# retros.net
KiCad netlist of a schematic drawn in Altium Designer
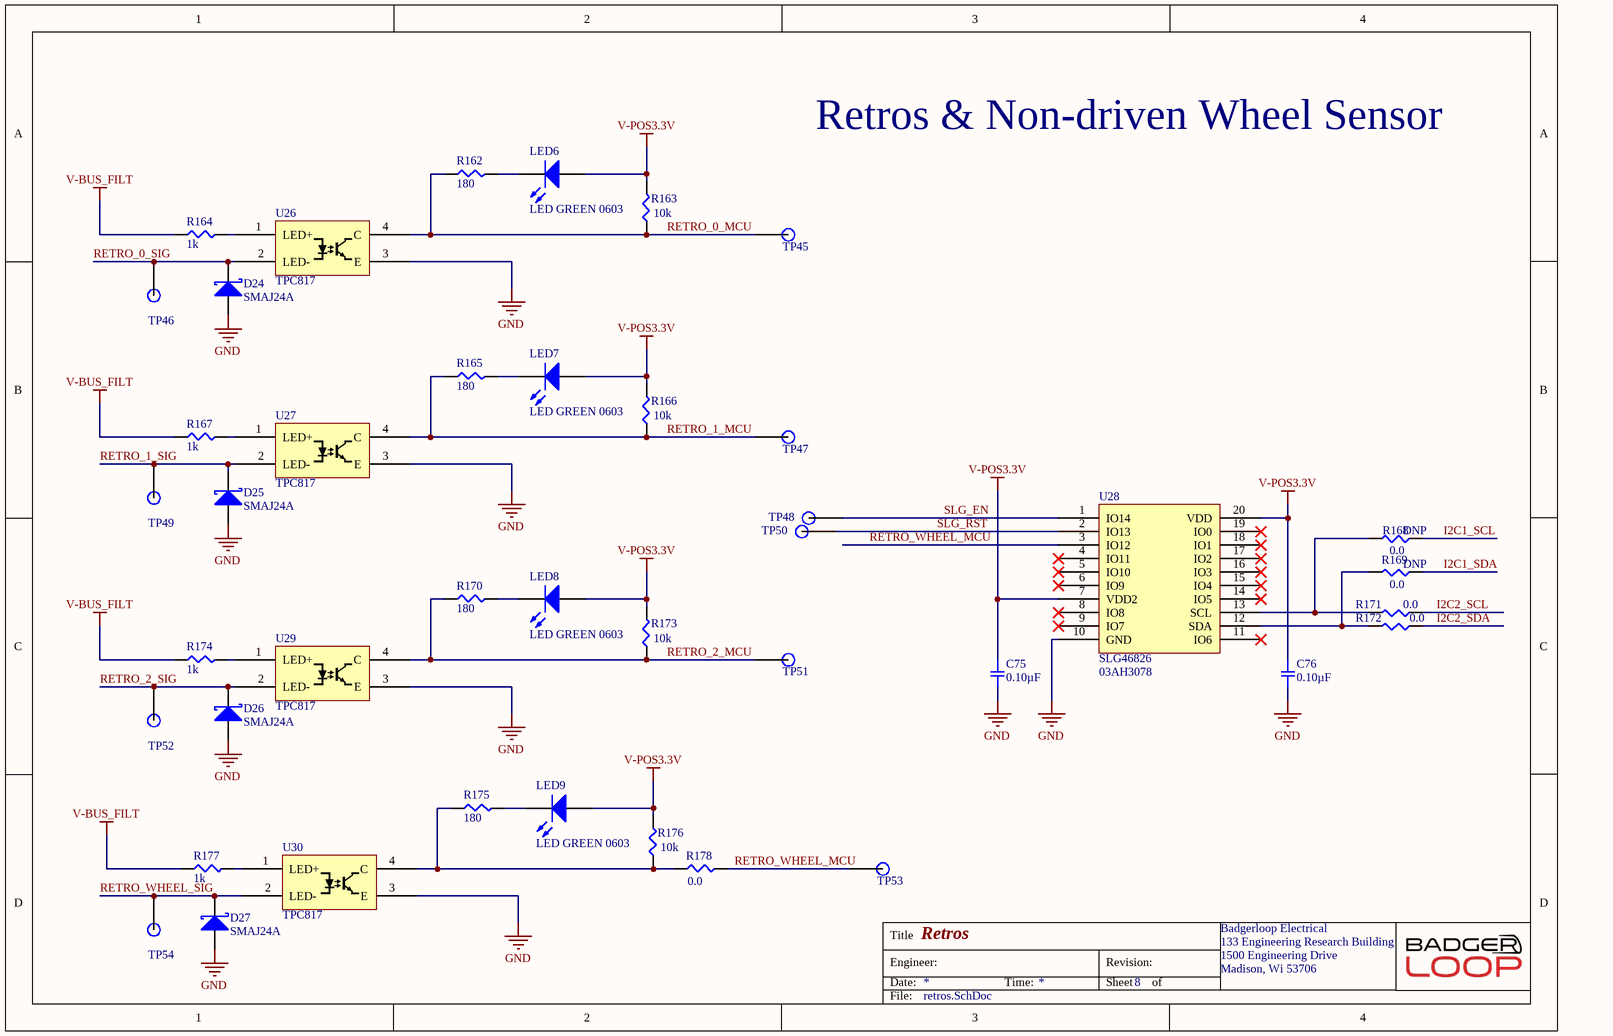
[diagram p0: retros.SchDoc]

(export (version "E")
  (design (tool "Eeschema 10.0.6"))
  (components
    (comp (ref "C75")
      (value "0.10µF")
      (footprint "SMD-0805C")
      (description "CAP CER 0.1UF 25V X7R 0805")
      (fields
        (field (name "DIGI-KEY PART NUMBER") "490-12754-1-ND")
        (field (name "PART NUMBER") "GRM219R71E104KA01D")
      )
      (libsource (lib "capacitors") (part "GRM219R71E104KA01D"))
    )
    (comp (ref "C76")
      (value "0.10µF")
      (footprint "SMD-0805C")
      (description "CAP CER 0.1UF 25V X7R 0805")
      (fields
        (field (name "DIGI-KEY PART NUMBER") "490-12754-1-ND")
        (field (name "PART NUMBER") "GRM219R71E104KA01D")
      )
      (libsource (lib "capacitors") (part "GRM219R71E104KA01D"))
    )
    (comp (ref "D24")
      (value "SMAJ24A")
      (footprint "INDM5026X18N")
      (description "TVS DIODE 24V 38.9V DO214AC")
      (fields (field (name "MANUFACTURER") "LittelFuse Inc"))
      (libsource (lib "misc") (part "SMAJ24A"))
    )
    (comp (ref "D25")
      (value "SMAJ24A")
      (footprint "INDM5026X18N")
      (description "TVS DIODE 24V 38.9V DO214AC")
      (fields (field (name "MANUFACTURER") "LittelFuse Inc"))
      (libsource (lib "misc") (part "SMAJ24A"))
    )
    (comp (ref "D26")
      (value "SMAJ24A")
      (footprint "INDM5026X18N")
      (description "TVS DIODE 24V 38.9V DO214AC")
      (fields (field (name "MANUFACTURER") "LittelFuse Inc"))
      (libsource (lib "misc") (part "SMAJ24A"))
    )
    (comp (ref "D27")
      (value "SMAJ24A")
      (footprint "INDM5026X18N")
      (description "TVS DIODE 24V 38.9V DO214AC")
      (fields (field (name "MANUFACTURER") "LittelFuse Inc"))
      (libsource (lib "misc") (part "SMAJ24A"))
    )
    (comp (ref "LED6")
      (value "LED GREEN 0603")
      (footprint "LED 0603 GREEN")
      (fields (field (name "MANUFACTURER") "Lite-On Inc."))
      (libsource (lib "misc") (part "LED GREEN 0603"))
    )
    (comp (ref "LED7")
      (value "LED GREEN 0603")
      (footprint "LED 0603 GREEN")
      (fields (field (name "MANUFACTURER") "Lite-On Inc."))
      (libsource (lib "misc") (part "LED GREEN 0603"))
    )
    (comp (ref "LED8")
      (value "LED GREEN 0603")
      (footprint "LED 0603 GREEN")
      (fields (field (name "MANUFACTURER") "Lite-On Inc."))
      (libsource (lib "misc") (part "LED GREEN 0603"))
    )
    (comp (ref "LED9")
      (value "LED GREEN 0603")
      (footprint "LED 0603 GREEN")
      (fields (field (name "MANUFACTURER") "Lite-On Inc."))
      (libsource (lib "misc") (part "LED GREEN 0603"))
    )
    (comp (ref "R162")
      (value "180")
      (footprint "SMD-0805-RES")
      (description "RES SMD 180 OHM 1% 1/8W 0805")
      (fields (field (name "PART NUMBER") "ERJ-6ENF1800V") (field (name "DIGI-KEY PART NUMBER") "P180CCT-ND"))
      (libsource (lib "resistors") (part "ERJ-6ENF1800V"))
    )
    (comp (ref "R163")
      (value "10k")
      (footprint "SMD-0805-RES")
      (description "RES SMD 10K OHM 5% 1/8W 0805")
      (fields (field (name "PART NUMBER") "ERJ-6GEYJ103V") (field (name "DIGI-KEY PART NUMBER") "P10KACT-ND"))
      (libsource (lib "resistors") (part "ERJ-6GEYJ103V"))
    )
    (comp (ref "R164")
      (value "1k")
      (footprint "SMD-0805-RES")
      (description "RES SMD 1K OHM 1% 1/8W 0805")
      (fields
        (field (name "PART NUMBER") "ERJ-6ENF1001V")
        (field (name "DIGI-KEY PART NUMBER") "P1.00KCCT-ND")
      )
      (libsource (lib "resistors") (part "ERJ-6ENF1001V"))
    )
    (comp (ref "R165")
      (value "180")
      (footprint "SMD-0805-RES")
      (description "RES SMD 180 OHM 1% 1/8W 0805")
      (fields (field (name "PART NUMBER") "ERJ-6ENF1800V") (field (name "DIGI-KEY PART NUMBER") "P180CCT-ND"))
      (libsource (lib "resistors") (part "ERJ-6ENF1800V"))
    )
    (comp (ref "R166")
      (value "10k")
      (footprint "SMD-0805-RES")
      (description "RES SMD 10K OHM 5% 1/8W 0805")
      (fields (field (name "PART NUMBER") "ERJ-6GEYJ103V") (field (name "DIGI-KEY PART NUMBER") "P10KACT-ND"))
      (libsource (lib "resistors") (part "ERJ-6GEYJ103V"))
    )
    (comp (ref "R167")
      (value "1k")
      (footprint "SMD-0805-RES")
      (description "RES SMD 1K OHM 1% 1/8W 0805")
      (fields
        (field (name "PART NUMBER") "ERJ-6ENF1001V")
        (field (name "DIGI-KEY PART NUMBER") "P1.00KCCT-ND")
      )
      (libsource (lib "resistors") (part "ERJ-6ENF1001V"))
    )
    (comp (ref "R168")
      (value "0.0")
      (footprint "SMD-0805-RES")
      (description "RES SMD 0.0 OHM JUMPER 1/8W 0805")
      (fields
        (field (name "PART NUMBER") "ERJ-6GEY0R00V")
        (field (name "DIGI-KEY PART NUMBER") "P0.0ACT-ND")
        (field (name "DNP") "DNP")
      )
      (libsource (lib "resistors") (part "ERJ-6GEY0R00V"))
    )
    (comp (ref "R169")
      (value "0.0")
      (footprint "SMD-0805-RES")
      (description "RES SMD 0.0 OHM JUMPER 1/8W 0805")
      (fields
        (field (name "PART NUMBER") "ERJ-6GEY0R00V")
        (field (name "DIGI-KEY PART NUMBER") "P0.0ACT-ND")
        (field (name "DNP") "DNP")
      )
      (libsource (lib "resistors") (part "ERJ-6GEY0R00V"))
    )
    (comp (ref "R170")
      (value "180")
      (footprint "SMD-0805-RES")
      (description "RES SMD 180 OHM 1% 1/8W 0805")
      (fields (field (name "PART NUMBER") "ERJ-6ENF1800V") (field (name "DIGI-KEY PART NUMBER") "P180CCT-ND"))
      (libsource (lib "resistors") (part "ERJ-6ENF1800V"))
    )
    (comp (ref "R171")
      (value "0.0")
      (footprint "SMD-0805-RES")
      (description "RES SMD 0.0 OHM JUMPER 1/8W 0805")
      (fields (field (name "PART NUMBER") "ERJ-6GEY0R00V") (field (name "DIGI-KEY PART NUMBER") "P0.0ACT-ND"))
      (libsource (lib "resistors") (part "ERJ-6GEY0R00V"))
    )
    (comp (ref "R172")
      (value "0.0")
      (footprint "SMD-0805-RES")
      (description "RES SMD 0.0 OHM JUMPER 1/8W 0805")
      (fields (field (name "PART NUMBER") "ERJ-6GEY0R00V") (field (name "DIGI-KEY PART NUMBER") "P0.0ACT-ND"))
      (libsource (lib "resistors") (part "ERJ-6GEY0R00V"))
    )
    (comp (ref "R173")
      (value "10k")
      (footprint "SMD-0805-RES")
      (description "RES SMD 10K OHM 5% 1/8W 0805")
      (fields (field (name "PART NUMBER") "ERJ-6GEYJ103V") (field (name "DIGI-KEY PART NUMBER") "P10KACT-ND"))
      (libsource (lib "resistors") (part "ERJ-6GEYJ103V"))
    )
    (comp (ref "R174")
      (value "1k")
      (footprint "SMD-0805-RES")
      (description "RES SMD 1K OHM 1% 1/8W 0805")
      (fields
        (field (name "PART NUMBER") "ERJ-6ENF1001V")
        (field (name "DIGI-KEY PART NUMBER") "P1.00KCCT-ND")
      )
      (libsource (lib "resistors") (part "ERJ-6ENF1001V"))
    )
    (comp (ref "R175")
      (value "180")
      (footprint "SMD-0805-RES")
      (description "RES SMD 180 OHM 1% 1/8W 0805")
      (fields (field (name "PART NUMBER") "ERJ-6ENF1800V") (field (name "DIGI-KEY PART NUMBER") "P180CCT-ND"))
      (libsource (lib "resistors") (part "ERJ-6ENF1800V"))
    )
    (comp (ref "R176")
      (value "10k")
      (footprint "SMD-0805-RES")
      (description "RES SMD 10K OHM 5% 1/8W 0805")
      (fields (field (name "PART NUMBER") "ERJ-6GEYJ103V") (field (name "DIGI-KEY PART NUMBER") "P10KACT-ND"))
      (libsource (lib "resistors") (part "ERJ-6GEYJ103V"))
    )
    (comp (ref "R177")
      (value "1k")
      (footprint "SMD-0805-RES")
      (description "RES SMD 1K OHM 1% 1/8W 0805")
      (fields
        (field (name "PART NUMBER") "ERJ-6ENF1001V")
        (field (name "DIGI-KEY PART NUMBER") "P1.00KCCT-ND")
      )
      (libsource (lib "resistors") (part "ERJ-6ENF1001V"))
    )
    (comp (ref "R178")
      (value "0.0")
      (footprint "SMD-0805-RES")
      (description "RES SMD 0.0 OHM JUMPER 1/8W 0805")
      (fields (field (name "PART NUMBER") "ERJ-6GEY0R00V") (field (name "DIGI-KEY PART NUMBER") "P0.0ACT-ND"))
      (libsource (lib "resistors") (part "ERJ-6GEY0R00V"))
    )
    (comp (ref "TP45")
      (value "TP")
      (footprint "Test Point")
      (description "SMD TEST POINT")
      (libsource (lib "misc") (part "TP"))
    )
    (comp (ref "TP46")
      (value "TP")
      (footprint "Test Point")
      (description "SMD TEST POINT")
      (libsource (lib "misc") (part "TP"))
    )
    (comp (ref "TP47")
      (value "TP")
      (footprint "Test Point")
      (description "SMD TEST POINT")
      (libsource (lib "misc") (part "TP"))
    )
    (comp (ref "TP48")
      (value "TP")
      (footprint "Test Point")
      (description "SMD TEST POINT")
      (libsource (lib "misc") (part "TP"))
    )
    (comp (ref "TP49")
      (value "TP")
      (footprint "Test Point")
      (description "SMD TEST POINT")
      (libsource (lib "misc") (part "TP"))
    )
    (comp (ref "TP50")
      (value "TP")
      (footprint "Test Point")
      (description "SMD TEST POINT")
      (libsource (lib "misc") (part "TP"))
    )
    (comp (ref "TP51")
      (value "TP")
      (footprint "Test Point")
      (description "SMD TEST POINT")
      (libsource (lib "misc") (part "TP"))
    )
    (comp (ref "TP52")
      (value "TP")
      (footprint "Test Point")
      (description "SMD TEST POINT")
      (libsource (lib "misc") (part "TP"))
    )
    (comp (ref "TP53")
      (value "TP")
      (footprint "Test Point")
      (description "SMD TEST POINT")
      (libsource (lib "misc") (part "TP"))
    )
    (comp (ref "TP54")
      (value "TP")
      (footprint "Test Point")
      (description "SMD TEST POINT")
      (libsource (lib "misc") (part "TP"))
    )
    (comp (ref "U26")
      (value "TPC817")
      (footprint "SOT200P1005X328-5N")
      (description "OPTOISO 5KV TRANS 4SOP")
      (fields (field (name "MANUFACTURER") "Taiwan Semi"))
      (libsource (lib "ic") (part "TPC817"))
    )
    (comp (ref "U27")
      (value "TPC817")
      (footprint "SOT200P1005X328-5N")
      (description "OPTOISO 5KV TRANS 4SOP")
      (fields (field (name "MANUFACTURER") "Taiwan Semi"))
      (libsource (lib "ic") (part "TPC817"))
    )
    (comp (ref "U28")
      (value "SLG46826")
      (footprint "SOP65P640X175-20N")
      (description "GreenPAK Programmable Mixed Signal Matrix with In-System Programmability")
      (fields
        (field (name "MANUFACTURER") "Dialog Semiconductor")
        (field (name "MANUFACTURER PART NUMBER") "SLG46826V-SKT")
        (field (name "SUPPLIER PART NUMBER 1") "03AH3078")
      )
      (libsource (lib "ic") (part "SLG46826"))
    )
    (comp (ref "U29")
      (value "TPC817")
      (footprint "SOT200P1005X328-5N")
      (description "OPTOISO 5KV TRANS 4SOP")
      (fields (field (name "MANUFACTURER") "Taiwan Semi"))
      (libsource (lib "ic") (part "TPC817"))
    )
    (comp (ref "U30")
      (value "TPC817")
      (footprint "SOT200P1005X328-5N")
      (description "OPTOISO 5KV TRANS 4SOP")
      (fields (field (name "MANUFACTURER") "Taiwan Semi"))
      (libsource (lib "ic") (part "TPC817"))
    )
  )
  (nets
    (net (code "1") (name "/I2C1_SCL") (class "Default")
      (node (ref "R168") (pin "1") (pinfunction "1_1") (pintype "passive"))
    )
    (net (code "2") (name "/I2C1_SDA") (class "Default")
      (node (ref "R169") (pin "1") (pinfunction "1_1") (pintype "passive"))
    )
    (net (code "3") (name "/I2C2_SCL") (class "Default")
      (node (ref "R171") (pin "1") (pinfunction "1_1") (pintype "passive"))
    )
    (net (code "4") (name "/I2C2_SDA") (class "Default")
      (node (ref "R172") (pin "1") (pinfunction "1_1") (pintype "passive"))
    )
    (net (code "5") (name "/RETRO_0_MCU") (class "Default")
      (node (ref "R162") (pin "1") (pinfunction "1_1") (pintype "passive"))
      (node (ref "R163") (pin "1") (pinfunction "1_1") (pintype "passive"))
      (node (ref "TP45") (pin "1") (pinfunction "1_1") (pintype "passive"))
      (node (ref "U26") (pin "4") (pinfunction "C_4") (pintype "passive"))
    )
    (net (code "6") (name "/RETRO_0_SIG") (class "Default")
      (node (ref "D24") (pin "1") (pinfunction "A_1") (pintype "passive"))
      (node (ref "TP46") (pin "1") (pinfunction "1_1") (pintype "passive"))
      (node (ref "U26") (pin "2") (pinfunction "LED-_2") (pintype "passive"))
    )
    (net (code "7") (name "/RETRO_1_MCU") (class "Default")
      (node (ref "R165") (pin "1") (pinfunction "1_1") (pintype "passive"))
      (node (ref "R166") (pin "1") (pinfunction "1_1") (pintype "passive"))
      (node (ref "TP47") (pin "1") (pinfunction "1_1") (pintype "passive"))
      (node (ref "U27") (pin "4") (pinfunction "C_4") (pintype "passive"))
    )
    (net (code "8") (name "/RETRO_1_SIG") (class "Default")
      (node (ref "D25") (pin "1") (pinfunction "A_1") (pintype "passive"))
      (node (ref "TP49") (pin "1") (pinfunction "1_1") (pintype "passive"))
      (node (ref "U27") (pin "2") (pinfunction "LED-_2") (pintype "passive"))
    )
    (net (code "9") (name "/RETRO_2_MCU") (class "Default")
      (node (ref "R170") (pin "1") (pinfunction "1_1") (pintype "passive"))
      (node (ref "R173") (pin "1") (pinfunction "1_1") (pintype "passive"))
      (node (ref "TP51") (pin "1") (pinfunction "1_1") (pintype "passive"))
      (node (ref "U29") (pin "4") (pinfunction "C_4") (pintype "passive"))
    )
    (net (code "10") (name "/RETRO_2_SIG") (class "Default")
      (node (ref "D26") (pin "1") (pinfunction "A_1") (pintype "passive"))
      (node (ref "TP52") (pin "1") (pinfunction "1_1") (pintype "passive"))
      (node (ref "U29") (pin "2") (pinfunction "LED-_2") (pintype "passive"))
    )
    (net (code "11") (name "/RETRO_WHEEL_MCU") (class "Default")
      (node (ref "R178") (pin "2") (pinfunction "2_2") (pintype "passive"))
      (node (ref "TP53") (pin "1") (pinfunction "1_1") (pintype "passive"))
      (node (ref "U28") (pin "3") (pinfunction "IO12_3") (pintype "passive"))
    )
    (net (code "12") (name "/RETRO_WHEEL_SIG") (class "Default")
      (node (ref "D27") (pin "1") (pinfunction "A_1") (pintype "passive"))
      (node (ref "TP54") (pin "1") (pinfunction "1_1") (pintype "passive"))
      (node (ref "U30") (pin "2") (pinfunction "LED-_2") (pintype "passive"))
    )
    (net (code "13") (name "/SLG_EN") (class "Default")
      (node (ref "TP48") (pin "1") (pinfunction "1_1") (pintype "passive"))
      (node (ref "U28") (pin "1") (pinfunction "IO14_1") (pintype "passive"))
    )
    (net (code "14") (name "/SLG_RST") (class "Default")
      (node (ref "TP50") (pin "1") (pinfunction "1_1") (pintype "passive"))
      (node (ref "U28") (pin "2") (pinfunction "IO13_2") (pintype "passive"))
    )
    (net (code "15") (name "GND") (class "Default")
      (node (ref "C75") (pin "2") (pinfunction "2_2") (pintype "passive"))
      (node (ref "C76") (pin "2") (pinfunction "2_2") (pintype "passive"))
      (node (ref "D24") (pin "2") (pinfunction "K_2") (pintype "passive"))
      (node (ref "D25") (pin "2") (pinfunction "K_2") (pintype "passive"))
      (node (ref "D26") (pin "2") (pinfunction "K_2") (pintype "passive"))
      (node (ref "D27") (pin "2") (pinfunction "K_2") (pintype "passive"))
      (node (ref "U26") (pin "3") (pinfunction "E_3") (pintype "passive"))
      (node (ref "U27") (pin "3") (pinfunction "E_3") (pintype "passive"))
      (node (ref "U28") (pin "10") (pinfunction "GND_10") (pintype "passive"))
      (node (ref "U29") (pin "3") (pinfunction "E_3") (pintype "passive"))
      (node (ref "U30") (pin "3") (pinfunction "E_3") (pintype "passive"))
    )
    (net (code "16") (name "Net-(LED6-K)") (class "Default")
      (node (ref "LED6") (pin "2") (pinfunction "K_2") (pintype "passive"))
      (node (ref "R162") (pin "2") (pinfunction "2_2") (pintype "passive"))
    )
    (net (code "17") (name "Net-(LED7-K)") (class "Default")
      (node (ref "LED7") (pin "2") (pinfunction "K_2") (pintype "passive"))
      (node (ref "R165") (pin "2") (pinfunction "2_2") (pintype "passive"))
    )
    (net (code "18") (name "Net-(LED8-K)") (class "Default")
      (node (ref "LED8") (pin "2") (pinfunction "K_2") (pintype "passive"))
      (node (ref "R170") (pin "2") (pinfunction "2_2") (pintype "passive"))
    )
    (net (code "19") (name "Net-(LED9-K)") (class "Default")
      (node (ref "LED9") (pin "2") (pinfunction "K_2") (pintype "passive"))
      (node (ref "R175") (pin "2") (pinfunction "2_2") (pintype "passive"))
    )
    (net (code "20") (name "Net-(U26-LED+)") (class "Default")
      (node (ref "R164") (pin "2") (pinfunction "2_2") (pintype "passive"))
      (node (ref "U26") (pin "1") (pinfunction "LED+_1") (pintype "passive"))
    )
    (net (code "21") (name "Net-(U27-LED+)") (class "Default")
      (node (ref "R167") (pin "2") (pinfunction "2_2") (pintype "passive"))
      (node (ref "U27") (pin "1") (pinfunction "LED+_1") (pintype "passive"))
    )
    (net (code "22") (name "Net-(U28-SCL)") (class "Default")
      (node (ref "R168") (pin "2") (pinfunction "2_2") (pintype "passive"))
      (node (ref "R171") (pin "2") (pinfunction "2_2") (pintype "passive"))
      (node (ref "U28") (pin "13") (pinfunction "SCL_13") (pintype "passive"))
    )
    (net (code "23") (name "Net-(U28-SDA)") (class "Default")
      (node (ref "R169") (pin "2") (pinfunction "2_2") (pintype "passive"))
      (node (ref "R172") (pin "2") (pinfunction "2_2") (pintype "passive"))
      (node (ref "U28") (pin "12") (pinfunction "SDA_12") (pintype "passive"))
    )
    (net (code "24") (name "Net-(U29-LED+)") (class "Default")
      (node (ref "R174") (pin "2") (pinfunction "2_2") (pintype "passive"))
      (node (ref "U29") (pin "1") (pinfunction "LED+_1") (pintype "passive"))
    )
    (net (code "25") (name "Net-(U30-C)") (class "Default")
      (node (ref "R175") (pin "1") (pinfunction "1_1") (pintype "passive"))
      (node (ref "R176") (pin "1") (pinfunction "1_1") (pintype "passive"))
      (node (ref "R178") (pin "1") (pinfunction "1_1") (pintype "passive"))
      (node (ref "U30") (pin "4") (pinfunction "C_4") (pintype "passive"))
    )
    (net (code "26") (name "Net-(U30-LED+)") (class "Default")
      (node (ref "R177") (pin "2") (pinfunction "2_2") (pintype "passive"))
      (node (ref "U30") (pin "1") (pinfunction "LED+_1") (pintype "passive"))
    )
    (net (code "27") (name "V-BUS_FILT") (class "Default")
      (node (ref "R164") (pin "1") (pinfunction "1_1") (pintype "passive"))
      (node (ref "R167") (pin "1") (pinfunction "1_1") (pintype "passive"))
      (node (ref "R174") (pin "1") (pinfunction "1_1") (pintype "passive"))
      (node (ref "R177") (pin "1") (pinfunction "1_1") (pintype "passive"))
    )
    (net (code "28") (name "V-POS3.3V") (class "Default")
      (node (ref "C75") (pin "1") (pinfunction "1_1") (pintype "passive"))
      (node (ref "C76") (pin "1") (pinfunction "1_1") (pintype "passive"))
      (node (ref "LED6") (pin "1") (pinfunction "A_1") (pintype "passive"))
      (node (ref "LED7") (pin "1") (pinfunction "A_1") (pintype "passive"))
      (node (ref "LED8") (pin "1") (pinfunction "A_1") (pintype "passive"))
      (node (ref "LED9") (pin "1") (pinfunction "A_1") (pintype "passive"))
      (node (ref "R163") (pin "2") (pinfunction "2_2") (pintype "passive"))
      (node (ref "R166") (pin "2") (pinfunction "2_2") (pintype "passive"))
      (node (ref "R173") (pin "2") (pinfunction "2_2") (pintype "passive"))
      (node (ref "R176") (pin "2") (pinfunction "2_2") (pintype "passive"))
      (node (ref "U28") (pin "20") (pinfunction "VDD_20") (pintype "passive"))
      (node (ref "U28") (pin "7") (pinfunction "VDD2_7") (pintype "passive"))
    )
    (net (code "29") (name "unconnected-(U28-IO0-Pad19)") (class "Default")
      (node (ref "U28") (pin "19") (pinfunction "IO0_19") (pintype "passive+no_connect"))
    )
    (net (code "30") (name "unconnected-(U28-IO1-Pad18)") (class "Default")
      (node (ref "U28") (pin "18") (pinfunction "IO1_18") (pintype "passive+no_connect"))
    )
    (net (code "31") (name "unconnected-(U28-IO2-Pad17)") (class "Default")
      (node (ref "U28") (pin "17") (pinfunction "IO2_17") (pintype "passive+no_connect"))
    )
    (net (code "32") (name "unconnected-(U28-IO3-Pad16)") (class "Default")
      (node (ref "U28") (pin "16") (pinfunction "IO3_16") (pintype "passive+no_connect"))
    )
    (net (code "33") (name "unconnected-(U28-IO4-Pad15)") (class "Default")
      (node (ref "U28") (pin "15") (pinfunction "IO4_15") (pintype "passive+no_connect"))
    )
    (net (code "34") (name "unconnected-(U28-IO5-Pad14)") (class "Default")
      (node (ref "U28") (pin "14") (pinfunction "IO5_14") (pintype "passive+no_connect"))
    )
    (net (code "35") (name "unconnected-(U28-IO6-Pad11)") (class "Default")
      (node (ref "U28") (pin "11") (pinfunction "IO6_11") (pintype "passive+no_connect"))
    )
    (net (code "36") (name "unconnected-(U28-IO7-Pad9)") (class "Default")
      (node (ref "U28") (pin "9") (pinfunction "IO7_9") (pintype "passive+no_connect"))
    )
    (net (code "37") (name "unconnected-(U28-IO8-Pad8)") (class "Default")
      (node (ref "U28") (pin "8") (pinfunction "IO8_8") (pintype "passive+no_connect"))
    )
    (net (code "38") (name "unconnected-(U28-IO9-Pad6)") (class "Default")
      (node (ref "U28") (pin "6") (pinfunction "IO9_6") (pintype "passive+no_connect"))
    )
    (net (code "39") (name "unconnected-(U28-IO10-Pad5)") (class "Default")
      (node (ref "U28") (pin "5") (pinfunction "IO10_5") (pintype "passive+no_connect"))
    )
    (net (code "40") (name "unconnected-(U28-IO11-Pad4)") (class "Default")
      (node (ref "U28") (pin "4") (pinfunction "IO11_4") (pintype "passive+no_connect"))
    )
  )
)
